# Meas_Channel.net
KiCad netlist of a schematic drawn in Altium Designer
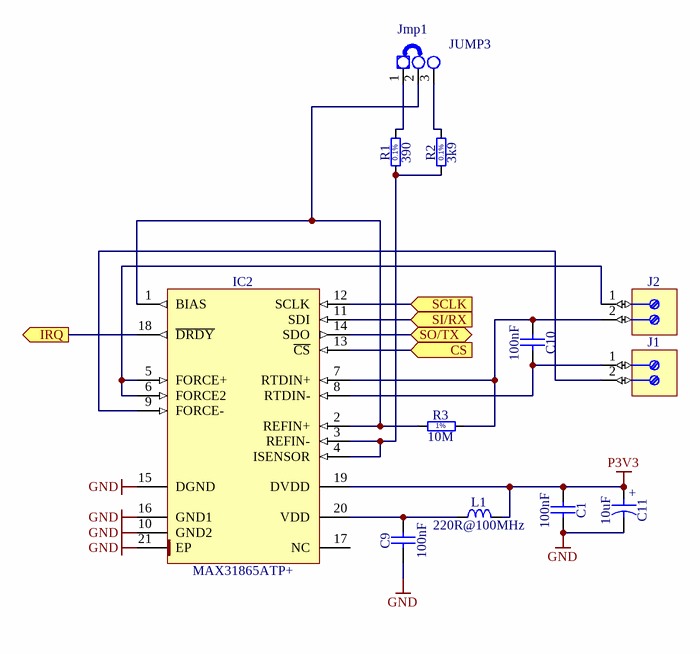
[diagram p0: Meas_Channel.SchDoc]

(export (version "E")
  (design (tool "Eeschema 10.0.6"))
  (components
    (comp (ref "C1")
      (value "100nF")
      (footprint "CAPC1005X55N")
      (description "Non-polarised capacitor")
      (fields
        (field (name "PART NUMBER") "CC0402_100NF_16V_10%_X5R")
        (field (name "VOLTAGE") "16V")
        (field (name "AUTHOR") "CERN DEM JLC")
      )
      (libsource (lib "Capacitors") (part "Capacitor - non polarized"))
    )
    (comp (ref "C9")
      (value "100nF")
      (footprint "CAPC1005X55N")
      (description "Non-polarised capacitor")
      (fields
        (field (name "PART NUMBER") "CC0402_100NF_16V_10%_X5R")
        (field (name "VOLTAGE") "16V")
        (field (name "AUTHOR") "CERN DEM JLC")
      )
      (libsource (lib "Capacitors") (part "Capacitor - non polarized"))
    )
    (comp (ref "C10")
      (value "100nF")
      (footprint "CAPC1005X55N")
      (description "Non-polarised capacitor")
      (fields
        (field (name "PART NUMBER") "CC0402_100NF_16V_10%_X5R")
        (field (name "VOLTAGE") "16V")
        (field (name "AUTHOR") "CERN DEM JLC")
      )
      (libsource (lib "Capacitors") (part "Capacitor - non polarized"))
    )
    (comp (ref "C11")
      (value "10uF")
      (footprint "CAPMP3216X180N")
      (description "Polarised capacitor")
      (fields
        (field (name "PART NUMBER") "CTE3216-18_10UF_16V_20%_AVX_TCJ")
        (field (name "VOLTAGE") "16V")
        (field (name "AUTHOR") "CERN DEM JLC")
      )
      (libsource (lib "Capacitors") (part "Capacitor - polarized"))
    )
    (comp (ref "IC2")
      (value "MAX31865ATP+")
      (footprint "QFN65P500X500X80-21N-S335")
      (description "RTD-to-Digital Converter")
      (fields (field (name "MANUFACTURER") "MAXIM") (field (name "AUTHOR") "CERN DEM MR"))
      (libsource (lib "ICs And Semiconductors") (part "MAX31865ATP+"))
    )
    (comp (ref "J1")
      (value "~")
      (footprint "PHOENIX_1725656")
      (description "Terminal Block, 2 Positions, Screw Connection")
      (fields
        (field (name "PART NUMBER") "PHOENIX_1725656")
        (field (name "MANUFACTURER") "PHOENIX CONTACT")
        (field (name "AUTHOR") "CERN DEM JMW")
      )
      (libsource (lib "Connectors") (part "Terminal Block_2 Positions_Screw Connection"))
    )
    (comp (ref "J2")
      (value "~")
      (footprint "PHOENIX_1725656")
      (description "Terminal Block, 2 Positions, Screw Connection")
      (fields
        (field (name "PART NUMBER") "PHOENIX_1725656")
        (field (name "MANUFACTURER") "PHOENIX CONTACT")
        (field (name "AUTHOR") "CERN DEM JMW")
      )
      (libsource (lib "Connectors") (part "Terminal Block_2 Positions_Screw Connection"))
    )
    (comp (ref "Jmp1") (value "JUMP3") (footprint "jump3") (libsource (lib "LIBRARY_SCH") (part "JUMP3")))
    (comp (ref "L1")
      (value "220R@100MHz")
      (footprint "INDC1005X55N")
      (description "Inductor")
      (fields
        (field (name "PART NUMBER") "IND0402_MURATA_BLM15HB221SN1")
        (field (name "POWER") "250mA")
        (field (name "AUTHOR") "CERN DEM JLC")
      )
      (libsource (lib "Inductors & Transformers") (part "Inductor"))
    )
    (comp (ref "R1")
      (value "390")
      (footprint "RESC3216X65N")
      (description "Resistor - 0.1%")
      (fields
        (field (name "PART NUMBER") "R1206_390R_0.1%_0.25W_25PPM")
        (field (name "POWER") "0.25W")
        (field (name "AUTHOR") "CERN DEM JLC")
      )
      (libsource (lib "Resistors") (part "Resistor - 0.1%"))
    )
    (comp (ref "R2")
      (value "3k9")
      (footprint "RESC3216X65N")
      (description "Resistor - 0.1%")
      (fields
        (field (name "PART NUMBER") "R1206_3K9_0.1%_0.25W_25PPM")
        (field (name "POWER") "0.25W")
        (field (name "AUTHOR") "CERN DEM JLC")
      )
      (libsource (lib "Resistors") (part "Resistor - 0.1%"))
    )
    (comp (ref "R3")
      (value "10M")
      (footprint "RESC1608X55N")
      (description "Resistor - 1%")
      (fields
        (field (name "PART NUMBER") "R0603_10M_1%_0.1W_100PPM")
        (field (name "POWER") "0.1W")
        (field (name "AUTHOR") "CERN DEM JLC")
      )
      (libsource (lib "Resistors") (part "Resistor - 1%"))
    )
  )
  (nets
    (net (code "1") (name "/CS") (class "Default")
      (node (ref "IC2") (pin "13") (pinfunction "~{CS}_13") (pintype "input"))
    )
    (net (code "2") (name "/IRQ") (class "Default")
      (node (ref "IC2") (pin "18") (pinfunction "~{DRDY}_18") (pintype "output"))
    )
    (net (code "3") (name "/SCLK") (class "Default")
      (node (ref "IC2") (pin "12") (pinfunction "SCLK_12") (pintype "input"))
    )
    (net (code "4") (name "/SI{slash}RX") (class "Default")
      (node (ref "IC2") (pin "11") (pinfunction "SDI_11") (pintype "input"))
    )
    (net (code "5") (name "/SO{slash}TX") (class "Default")
      (node (ref "IC2") (pin "14") (pinfunction "SDO_14") (pintype "output"))
    )
    (net (code "6") (name "GND") (class "Default")
      (node (ref "C1") (pin "2") (pinfunction "2_2") (pintype "passive"))
      (node (ref "C11") (pin "2") (pinfunction "2_2") (pintype "passive"))
      (node (ref "C9") (pin "1") (pinfunction "1_1") (pintype "passive"))
      (node (ref "IC2") (pin "10") (pinfunction "GND2_10") (pintype "power_in"))
      (node (ref "IC2") (pin "15") (pinfunction "DGND_15") (pintype "power_in"))
      (node (ref "IC2") (pin "16") (pinfunction "GND1_16") (pintype "power_in"))
      (node (ref "IC2") (pin "21") (pinfunction "EP_21") (pintype "power_in"))
    )
    (net (code "7") (name "Net-(IC2-BIAS)") (class "Default")
      (node (ref "IC2") (pin "1") (pinfunction "BIAS_1") (pintype "output"))
      (node (ref "IC2") (pin "2") (pinfunction "REFIN+_2") (pintype "input"))
      (node (ref "Jmp1") (pin "2") (pintype "passive"))
      (node (ref "R3") (pin "1") (pinfunction "1_1") (pintype "passive"))
    )
    (net (code "8") (name "Net-(IC2-FORCE+)") (class "Default")
      (node (ref "IC2") (pin "5") (pinfunction "FORCE+_5") (pintype "input"))
      (node (ref "IC2") (pin "6") (pinfunction "FORCE2_6") (pintype "input"))
      (node (ref "J2") (pin "1") (pinfunction "1_1") (pintype "bidirectional"))
    )
    (net (code "9") (name "Net-(IC2-FORCE-)") (class "Default")
      (node (ref "IC2") (pin "9") (pinfunction "FORCE-_9") (pintype "input"))
      (node (ref "J1") (pin "2") (pinfunction "2_2") (pintype "bidirectional"))
    )
    (net (code "10") (name "Net-(IC2-ISENSOR)") (class "Default")
      (node (ref "IC2") (pin "3") (pinfunction "REFIN-_3") (pintype "input"))
      (node (ref "IC2") (pin "4") (pinfunction "ISENSOR_4") (pintype "input"))
      (node (ref "R1") (pin "1") (pinfunction "1_1") (pintype "passive"))
      (node (ref "R2") (pin "1") (pinfunction "1_1") (pintype "passive"))
    )
    (net (code "11") (name "Net-(IC2-RTDIN+)") (class "Default")
      (node (ref "C10") (pin "1") (pinfunction "1_1") (pintype "passive"))
      (node (ref "IC2") (pin "7") (pinfunction "RTDIN+_7") (pintype "input"))
      (node (ref "J2") (pin "2") (pinfunction "2_2") (pintype "bidirectional"))
      (node (ref "R3") (pin "2") (pinfunction "2_2") (pintype "passive"))
    )
    (net (code "12") (name "Net-(IC2-RTDIN-)") (class "Default")
      (node (ref "C10") (pin "2") (pinfunction "2_2") (pintype "passive"))
      (node (ref "IC2") (pin "8") (pinfunction "RTDIN-_8") (pintype "input"))
      (node (ref "J1") (pin "1") (pinfunction "1_1") (pintype "bidirectional"))
    )
    (net (code "13") (name "Net-(IC2-VDD)") (class "Default")
      (node (ref "C9") (pin "2") (pinfunction "2_2") (pintype "passive"))
      (node (ref "IC2") (pin "20") (pinfunction "VDD_20") (pintype "power_in"))
      (node (ref "L1") (pin "1") (pinfunction "1_1") (pintype "passive"))
    )
    (net (code "14") (name "Net-(Jmp1-Pad1)") (class "Default")
      (node (ref "Jmp1") (pin "1") (pintype "passive"))
      (node (ref "R1") (pin "2") (pinfunction "2_2") (pintype "passive"))
    )
    (net (code "15") (name "Net-(Jmp1-Pad3)") (class "Default")
      (node (ref "Jmp1") (pin "3") (pintype "passive"))
      (node (ref "R2") (pin "2") (pinfunction "2_2") (pintype "passive"))
    )
    (net (code "16") (name "P3V3") (class "Default")
      (node (ref "C1") (pin "1") (pinfunction "1_1") (pintype "passive"))
      (node (ref "C11") (pin "1") (pinfunction "1_1") (pintype "passive"))
      (node (ref "IC2") (pin "19") (pinfunction "DVDD_19") (pintype "power_in"))
      (node (ref "L1") (pin "2") (pinfunction "2_2") (pintype "passive"))
    )
    (net (code "17") (name "unconnected-(IC2-NC-Pad17)") (class "Default")
      (node (ref "IC2") (pin "17") (pinfunction "NC_17") (pintype "passive"))
    )
  )
)
